# Micro_DSUB_IDC.net
KiCad netlist of a schematic drawn in Altium Designer
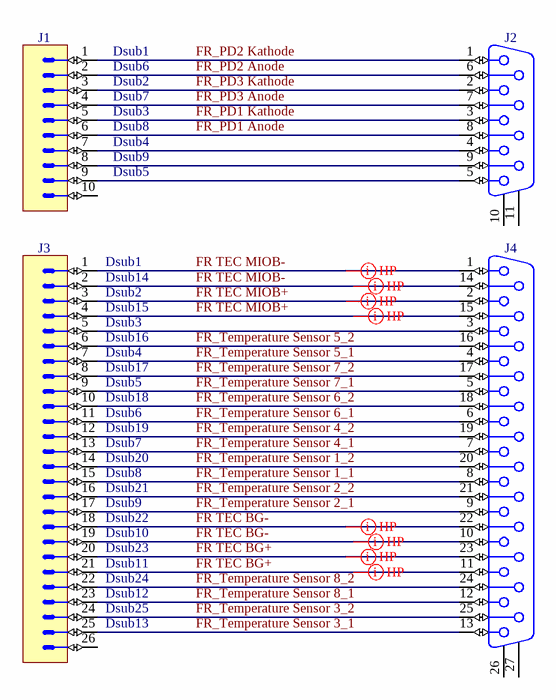
[diagram p0: Micro_DSUB_IDC.SchDoc]

(export (version "E")
  (design (tool "Eeschema 10.0.6"))
  (components
    (comp (ref "J1")
      (value "Header 10")
      (footprint "3M_N2510-6002RB")
      (description "Connector 10 Male")
      (fields
        (field (name "PART NUMBER") "3M_N2510-6002RB")
        (field (name "MANUFACTURER") "3M")
        (field (name "AUTHOR") "CERN DEM JLC")
      )
      (libsource (lib "Connectors") (part "Connector 10 Male"))
    )
    (comp (ref "J2")
      (value "MICRO D")
      (footprint "NORCOMP_380-009-213L001")
      (description "Connector D-sub 9 Female")
      (fields
        (field (name "PART NUMBER") "NORCOMP_380-009-213L001")
        (field (name "MANUFACTURER") "NORCOMP")
        (field (name "AUTHOR") "CERN DEM HF")
      )
      (libsource (lib "Connectors") (part "Connector D-sub 9 Female"))
    )
    (comp (ref "J3")
      (value "Header 26")
      (footprint "3M_N2526-6002RB")
      (description "Connector 26 Male")
      (fields
        (field (name "PART NUMBER") "3M_N2526-6002RB")
        (field (name "MANUFACTURER") "3M")
        (field (name "AUTHOR") "CERN DEM JLC")
      )
      (libsource (lib "Connectors") (part "Connector 26 Male"))
    )
    (comp (ref "J4")
      (value "MICRO D")
      (footprint "NORCOMP_380-025-213L001")
      (description "Connector D-sub 25 Female")
      (fields
        (field (name "PART NUMBER") "NORCOMP_380-025-213L001")
        (field (name "MANUFACTURER") "NORCOMP")
        (field (name "AUTHOR") "CERN DEM HF")
      )
      (libsource (lib "Connectors") (part "Connector D-sub 25 Female"))
    )
  )
  (nets
    (net (code "1") (name "/FR TEC BG+") (class "Default")
      (node (ref "J3") (pin "20") (pinfunction "20_20") (pintype "bidirectional"))
      (node (ref "J3") (pin "21") (pinfunction "21_21") (pintype "bidirectional"))
      (node (ref "J4") (pin "11") (pinfunction "11_11") (pintype "bidirectional"))
      (node (ref "J4") (pin "23") (pinfunction "23_23") (pintype "bidirectional"))
    )
    (net (code "2") (name "/FR TEC BG-") (class "Default")
      (node (ref "J3") (pin "18") (pinfunction "18_18") (pintype "bidirectional"))
      (node (ref "J3") (pin "19") (pinfunction "19_19") (pintype "bidirectional"))
      (node (ref "J4") (pin "10") (pinfunction "10_10") (pintype "bidirectional"))
      (node (ref "J4") (pin "22") (pinfunction "22_22") (pintype "bidirectional"))
    )
    (net (code "3") (name "/FR TEC MIOB+") (class "Default")
      (node (ref "J3") (pin "3") (pinfunction "3_3") (pintype "bidirectional"))
      (node (ref "J3") (pin "4") (pinfunction "4_4") (pintype "bidirectional"))
      (node (ref "J4") (pin "15") (pinfunction "15_15") (pintype "bidirectional"))
      (node (ref "J4") (pin "2") (pinfunction "2_2") (pintype "bidirectional"))
    )
    (net (code "4") (name "/FR TEC MIOB-") (class "Default")
      (node (ref "J3") (pin "1") (pinfunction "1_1") (pintype "bidirectional"))
      (node (ref "J3") (pin "2") (pinfunction "2_2") (pintype "bidirectional"))
      (node (ref "J4") (pin "1") (pinfunction "1_1") (pintype "bidirectional"))
      (node (ref "J4") (pin "14") (pinfunction "14_14") (pintype "bidirectional"))
    )
    (net (code "5") (name "/FR_PD1 Anode") (class "Default")
      (node (ref "J1") (pin "6") (pinfunction "6_6") (pintype "bidirectional"))
      (node (ref "J2") (pin "8") (pinfunction "8_8") (pintype "bidirectional"))
    )
    (net (code "6") (name "/FR_PD1 Kathode") (class "Default")
      (node (ref "J1") (pin "5") (pinfunction "5_5") (pintype "bidirectional"))
      (node (ref "J2") (pin "3") (pinfunction "3_3") (pintype "bidirectional"))
    )
    (net (code "7") (name "/FR_PD2 Anode") (class "Default")
      (node (ref "J1") (pin "2") (pinfunction "2_2") (pintype "bidirectional"))
      (node (ref "J2") (pin "6") (pinfunction "6_6") (pintype "bidirectional"))
    )
    (net (code "8") (name "/FR_PD2 Kathode") (class "Default")
      (node (ref "J1") (pin "1") (pinfunction "1_1") (pintype "bidirectional"))
      (node (ref "J2") (pin "1") (pinfunction "1_1") (pintype "bidirectional"))
    )
    (net (code "9") (name "/FR_PD3 Anode") (class "Default")
      (node (ref "J1") (pin "4") (pinfunction "4_4") (pintype "bidirectional"))
      (node (ref "J2") (pin "7") (pinfunction "7_7") (pintype "bidirectional"))
    )
    (net (code "10") (name "/FR_PD3 Kathode") (class "Default")
      (node (ref "J1") (pin "3") (pinfunction "3_3") (pintype "bidirectional"))
      (node (ref "J2") (pin "2") (pinfunction "2_2") (pintype "bidirectional"))
    )
    (net (code "11") (name "/FR_Temperature Sensor 1_1") (class "Default")
      (node (ref "J3") (pin "15") (pinfunction "15_15") (pintype "bidirectional"))
      (node (ref "J4") (pin "8") (pinfunction "8_8") (pintype "bidirectional"))
    )
    (net (code "12") (name "/FR_Temperature Sensor 1_2") (class "Default")
      (node (ref "J3") (pin "14") (pinfunction "14_14") (pintype "bidirectional"))
      (node (ref "J4") (pin "20") (pinfunction "20_20") (pintype "bidirectional"))
    )
    (net (code "13") (name "/FR_Temperature Sensor 2_1") (class "Default")
      (node (ref "J3") (pin "17") (pinfunction "17_17") (pintype "bidirectional"))
      (node (ref "J4") (pin "9") (pinfunction "9_9") (pintype "bidirectional"))
    )
    (net (code "14") (name "/FR_Temperature Sensor 2_2") (class "Default")
      (node (ref "J3") (pin "16") (pinfunction "16_16") (pintype "bidirectional"))
      (node (ref "J4") (pin "21") (pinfunction "21_21") (pintype "bidirectional"))
    )
    (net (code "15") (name "/FR_Temperature Sensor 3_1") (class "Default")
      (node (ref "J3") (pin "25") (pinfunction "25_25") (pintype "bidirectional"))
      (node (ref "J4") (pin "13") (pinfunction "13_13") (pintype "bidirectional"))
    )
    (net (code "16") (name "/FR_Temperature Sensor 3_2") (class "Default")
      (node (ref "J3") (pin "24") (pinfunction "24_24") (pintype "bidirectional"))
      (node (ref "J4") (pin "25") (pinfunction "25_25") (pintype "bidirectional"))
    )
    (net (code "17") (name "/FR_Temperature Sensor 4_1") (class "Default")
      (node (ref "J3") (pin "13") (pinfunction "13_13") (pintype "bidirectional"))
      (node (ref "J4") (pin "7") (pinfunction "7_7") (pintype "bidirectional"))
    )
    (net (code "18") (name "/FR_Temperature Sensor 4_2") (class "Default")
      (node (ref "J3") (pin "12") (pinfunction "12_12") (pintype "bidirectional"))
      (node (ref "J4") (pin "19") (pinfunction "19_19") (pintype "bidirectional"))
    )
    (net (code "19") (name "/FR_Temperature Sensor 5_1") (class "Default")
      (node (ref "J3") (pin "7") (pinfunction "7_7") (pintype "bidirectional"))
      (node (ref "J4") (pin "4") (pinfunction "4_4") (pintype "bidirectional"))
    )
    (net (code "20") (name "/FR_Temperature Sensor 5_2") (class "Default")
      (node (ref "J3") (pin "6") (pinfunction "6_6") (pintype "bidirectional"))
      (node (ref "J4") (pin "16") (pinfunction "16_16") (pintype "bidirectional"))
    )
    (net (code "21") (name "/FR_Temperature Sensor 6_1") (class "Default")
      (node (ref "J3") (pin "11") (pinfunction "11_11") (pintype "bidirectional"))
      (node (ref "J4") (pin "6") (pinfunction "6_6") (pintype "bidirectional"))
    )
    (net (code "22") (name "/FR_Temperature Sensor 6_2") (class "Default")
      (node (ref "J3") (pin "10") (pinfunction "10_10") (pintype "bidirectional"))
      (node (ref "J4") (pin "18") (pinfunction "18_18") (pintype "bidirectional"))
    )
    (net (code "23") (name "/FR_Temperature Sensor 7_1") (class "Default")
      (node (ref "J3") (pin "9") (pinfunction "9_9") (pintype "bidirectional"))
      (node (ref "J4") (pin "5") (pinfunction "5_5") (pintype "bidirectional"))
    )
    (net (code "24") (name "/FR_Temperature Sensor 7_2") (class "Default")
      (node (ref "J3") (pin "8") (pinfunction "8_8") (pintype "bidirectional"))
      (node (ref "J4") (pin "17") (pinfunction "17_17") (pintype "bidirectional"))
    )
    (net (code "25") (name "/FR_Temperature Sensor 8_1") (class "Default")
      (node (ref "J3") (pin "23") (pinfunction "23_23") (pintype "bidirectional"))
      (node (ref "J4") (pin "12") (pinfunction "12_12") (pintype "bidirectional"))
    )
    (net (code "26") (name "/FR_Temperature Sensor 8_2") (class "Default")
      (node (ref "J3") (pin "22") (pinfunction "22_22") (pintype "bidirectional"))
      (node (ref "J4") (pin "24") (pinfunction "24_24") (pintype "bidirectional"))
    )
    (net (code "27") (name "Net-(J1-Pad7)") (class "Default")
      (node (ref "J1") (pin "7") (pinfunction "7_7") (pintype "bidirectional"))
      (node (ref "J2") (pin "4") (pinfunction "4_4") (pintype "bidirectional"))
    )
    (net (code "28") (name "Net-(J1-Pad8)") (class "Default")
      (node (ref "J1") (pin "8") (pinfunction "8_8") (pintype "bidirectional"))
      (node (ref "J2") (pin "9") (pinfunction "9_9") (pintype "bidirectional"))
    )
    (net (code "29") (name "Net-(J1-Pad9)") (class "Default")
      (node (ref "J1") (pin "9") (pinfunction "9_9") (pintype "bidirectional"))
      (node (ref "J2") (pin "5") (pinfunction "5_5") (pintype "bidirectional"))
    )
    (net (code "30") (name "Net-(J3-Pad5)") (class "Default")
      (node (ref "J3") (pin "5") (pinfunction "5_5") (pintype "bidirectional"))
      (node (ref "J4") (pin "3") (pinfunction "3_3") (pintype "bidirectional"))
    )
    (net (code "31") (name "unconnected-(J1-Pad10)") (class "Default")
      (node (ref "J1") (pin "10") (pinfunction "10_10") (pintype "bidirectional"))
    )
    (net (code "32") (name "unconnected-(J2-Pad10)") (class "Default")
      (node (ref "J2") (pin "10") (pinfunction "10_10") (pintype "passive"))
    )
    (net (code "33") (name "unconnected-(J2-Pad11)") (class "Default")
      (node (ref "J2") (pin "11") (pinfunction "11_11") (pintype "passive"))
    )
    (net (code "34") (name "unconnected-(J3-Pad26)") (class "Default")
      (node (ref "J3") (pin "26") (pinfunction "26_26") (pintype "bidirectional"))
    )
    (net (code "35") (name "unconnected-(J4-Pad26)") (class "Default")
      (node (ref "J4") (pin "26") (pinfunction "26_26") (pintype "passive"))
    )
    (net (code "36") (name "unconnected-(J4-Pad27)") (class "Default")
      (node (ref "J4") (pin "27") (pinfunction "27_27") (pintype "passive"))
    )
  )
)
